# SystemControlCard.net
KiCad netlist of a schematic drawn in EAGLE
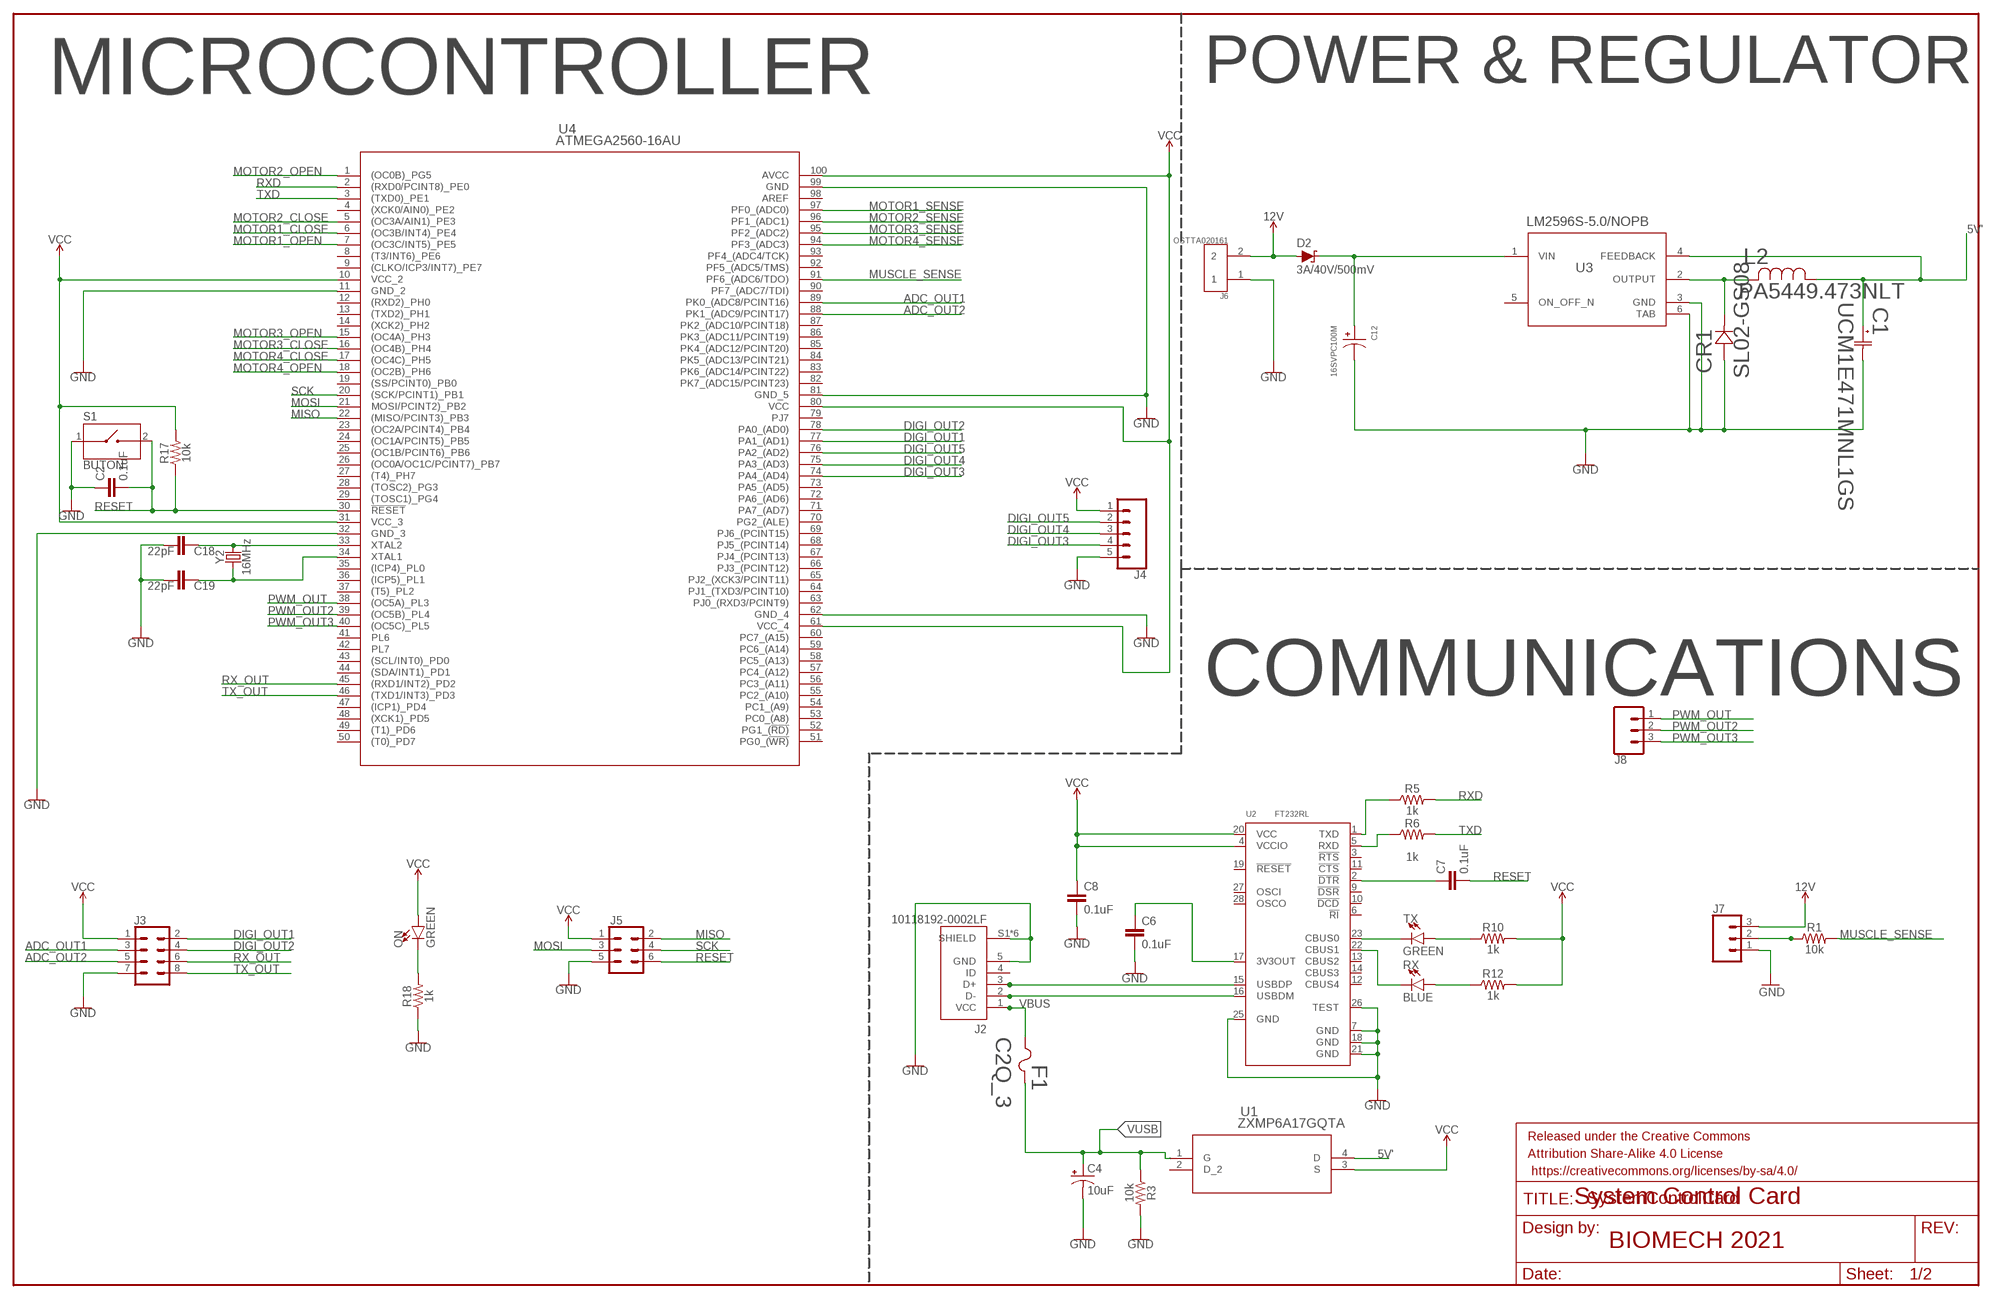
[diagram p0: schematic, sheet 1]
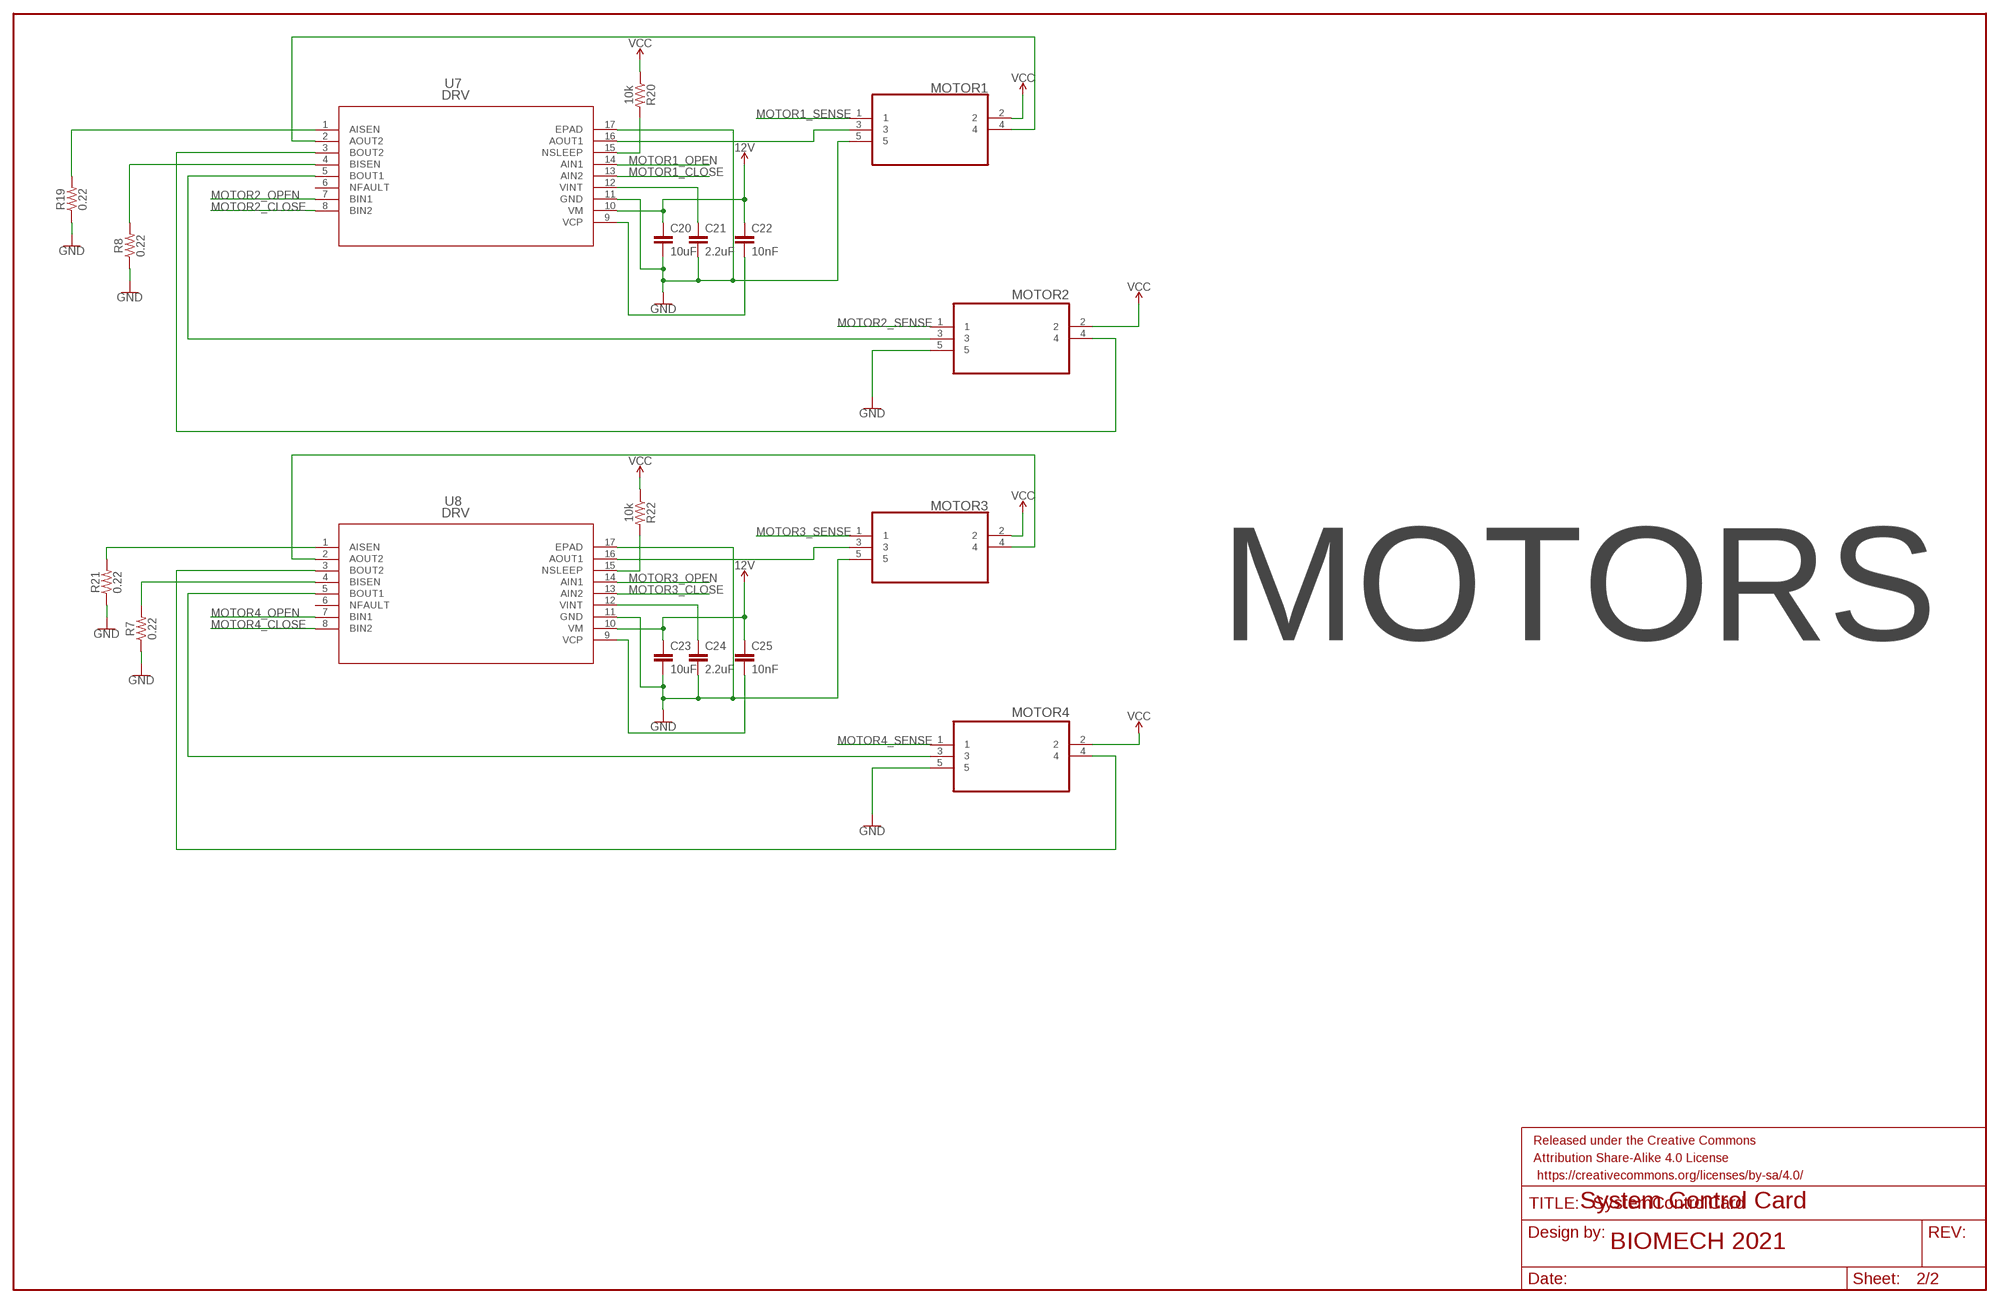
[diagram p1: schematic, sheet 2]

(export (version "E")
  (design (tool "Eeschema 10.0.6"))
  (components
    (comp (ref "C20")
      (value "10uF")
      (footprint "eagle-import:0603")
      (libsource (lib "eagle-import") (part "10UF-0603-6.3V-20%"))
    )
    (comp (ref "C21")
      (value "2.2uF")
      (footprint "eagle-import:0603")
      (libsource (lib "eagle-import") (part "2.2UF-0603-10V-20%"))
    )
    (comp (ref "C22")
      (value "10nF")
      (footprint "eagle-import:0603")
      (libsource (lib "eagle-import") (part "10NF-0603-50V-10%"))
    )
    (comp (ref "C23")
      (value "10uF")
      (footprint "eagle-import:0603")
      (libsource (lib "eagle-import") (part "10UF-0603-6.3V-20%"))
    )
    (comp (ref "C24")
      (value "2.2uF")
      (footprint "eagle-import:0603")
      (libsource (lib "eagle-import") (part "2.2UF-0603-10V-20%"))
    )
    (comp (ref "C25")
      (value "10nF")
      (footprint "eagle-import:0603")
      (libsource (lib "eagle-import") (part "10NF-0603-50V-10%"))
    )
    (comp (ref "FRAME1")
      (value "FRAME-LEDGER")
      (footprint "eagle-import:CREATIVE_COMMONS")
      (fields (field (name "DESIGNED_BY") "BIOMECH 2021") (field (name "TITLE") "System Control Card"))
      (libsource (lib "eagle-import") (part "FRAME-LEDGER"))
    )
    (comp (ref "MOTOR1")
      (value "SFW5R-1STE1LF")
      (footprint "eagle-import:FCI_SFW5R-1STE1LF")
      (fields (field (name "MF") "Amphenol ICC"))
      (libsource (lib "eagle-import") (part "SFW5R-1STE1LF"))
    )
    (comp (ref "MOTOR2")
      (value "SFW5R-1STE1LF")
      (footprint "eagle-import:FCI_SFW5R-1STE1LF")
      (fields (field (name "MF") "Amphenol ICC"))
      (libsource (lib "eagle-import") (part "SFW5R-1STE1LF"))
    )
    (comp (ref "MOTOR3")
      (value "SFW5R-1STE1LF")
      (footprint "eagle-import:FCI_SFW5R-1STE1LF")
      (fields (field (name "MF") "Amphenol ICC"))
      (libsource (lib "eagle-import") (part "SFW5R-1STE1LF"))
    )
    (comp (ref "MOTOR4")
      (value "SFW5R-1STE1LF")
      (footprint "eagle-import:FCI_SFW5R-1STE1LF")
      (fields (field (name "MF") "Amphenol ICC"))
      (libsource (lib "eagle-import") (part "SFW5R-1STE1LF"))
    )
    (comp (ref "R7")
      (value "0.22")
      (footprint "eagle-import:0805")
      (libsource (lib "eagle-import") (part "0.22OHM-0805-1/4W-1%"))
    )
    (comp (ref "R8")
      (value "0.22")
      (footprint "eagle-import:0805")
      (libsource (lib "eagle-import") (part "0.22OHM-0805-1/4W-1%"))
    )
    (comp (ref "R19")
      (value "0.22")
      (footprint "eagle-import:0805")
      (libsource (lib "eagle-import") (part "0.22OHM-0805-1/4W-1%"))
    )
    (comp (ref "R20")
      (value "10k")
      (footprint "eagle-import:0603")
      (libsource (lib "eagle-import") (part "10KOHM-0603-1/10W-1%"))
    )
    (comp (ref "R21")
      (value "0.22")
      (footprint "eagle-import:0805")
      (libsource (lib "eagle-import") (part "0.22OHM-0805-1/4W-1%"))
    )
    (comp (ref "R22")
      (value "10k")
      (footprint "eagle-import:0603")
      (libsource (lib "eagle-import") (part "10KOHM-0603-1/10W-1%"))
    )
    (comp (ref "U7")
      (value "DRV")
      (footprint "eagle-import:RTY16")
      (fields
        (field (name "GENERIC_PART_NUMBER") "DRV8833")
        (field (name "MANUFACTURER") "Texas Instruments")
        (field (name "MANUFACTURER_PART_NUMBER") "DRV8833RTYT")
      )
      (libsource (lib "eagle-import") (part "DRV8833RTYT"))
    )
    (comp (ref "U8")
      (value "DRV")
      (footprint "eagle-import:RTY16")
      (fields
        (field (name "GENERIC_PART_NUMBER") "DRV8833")
        (field (name "MANUFACTURER") "Texas Instruments")
        (field (name "MANUFACTURER_PART_NUMBER") "DRV8833RTYT")
      )
      (libsource (lib "eagle-import") (part "DRV8833RTYT"))
    )
    (comp (ref "C1")
      (value "UCM1E471MNL1GS")
      (footprint "eagle-import:CAP_UCD_8X10_NCH")
      (fields (field (name "COPYRIGHT") "Copyright (C) 2021 Ultra Librarian. All rights reserved."))
      (libsource (lib "eagle-import") (part "UCM1E471MNL1GS"))
    )
    (comp (ref "C2")
      (value "0.1uF")
      (footprint "eagle-import:0603")
      (libsource (lib "eagle-import") (part "0.1UF-0603-25V-5%"))
    )
    (comp (ref "C4")
      (value "10uF")
      (footprint "eagle-import:EIA3216")
      (libsource (lib "eagle-import") (part "10UF-POLAR-EIA3216-16V-10%(TANT)"))
    )
    (comp (ref "C6")
      (value "0.1uF")
      (footprint "eagle-import:0603")
      (libsource (lib "eagle-import") (part "0.1UF-0603-25V-5%"))
    )
    (comp (ref "C7")
      (value "0.1uF")
      (footprint "eagle-import:0603")
      (libsource (lib "eagle-import") (part "0.1UF-0603-25V-5%"))
    )
    (comp (ref "C8")
      (value "0.1uF")
      (footprint "eagle-import:0603")
      (libsource (lib "eagle-import") (part "0.1UF-0603-25V-5%"))
    )
    (comp (ref "C12")
      (value "16SVPC100M")
      (footprint "eagle-import:CAP_16SVPC100M")
      (fields (field (name "MF") "Panasonic"))
      (libsource (lib "eagle-import") (part "16SVPC100M"))
    )
    (comp (ref "C18")
      (value "22pF")
      (footprint "eagle-import:0603")
      (libsource (lib "eagle-import") (part "22PF-0603-50V-5%"))
    )
    (comp (ref "C19")
      (value "22pF")
      (footprint "eagle-import:0603")
      (libsource (lib "eagle-import") (part "22PF-0603-50V-5%"))
    )
    (comp (ref "CR1")
      (value "SL02-GS08")
      (footprint "eagle-import:DIODE_SL02-GS08_VIS")
      (fields (field (name "COPYRIGHT") "Copyright (C) 2021 Ultra Librarian. All rights reserved."))
      (libsource (lib "eagle-import") (part "SL02-GS08"))
    )
    (comp (ref "D2")
      (value "3A/40V/500mV")
      (footprint "eagle-import:SMA-DIODE")
      (libsource (lib "eagle-import") (part "DIODE-SCHOTTKY-B340A"))
    )
    (comp (ref "F1")
      (value "C2Q_3")
      (footprint "eagle-import:C2_BEL")
      (fields
        (field (name "MANUFACTURER_PART_NUMBER") "C2Q 3")
        (field (name "COPYRIGHT") "Copyright (C) 2021 Ultra Librarian. All rights reserved.")
      )
      (libsource (lib "eagle-import") (part "C2Q_3"))
    )
    (comp (ref "FRAME2")
      (value "FRAME-LEDGER")
      (footprint "eagle-import:CREATIVE_COMMONS")
      (fields (field (name "DESIGNED_BY") "BIOMECH 2021") (field (name "TITLE") "System Control Card"))
      (libsource (lib "eagle-import") (part "FRAME-LEDGER"))
    )
    (comp (ref "J2")
      (value "10118192-0002LF")
      (footprint "eagle-import:AMPHENOL_10118192-0002LF")
      (fields (field (name "MF") "Amphenol ICC"))
      (libsource (lib "eagle-import") (part "10118192-0002LF"))
    )
    (comp (ref "J3")
      (value "CONN_04X2")
      (footprint "eagle-import:2X4")
      (libsource (lib "eagle-import") (part "CONN_04X2"))
    )
    (comp (ref "J4")
      (value "CONN_05NO_SILK")
      (footprint "eagle-import:1X05_NO_SILK")
      (libsource (lib "eagle-import") (part "CONN_05NO_SILK"))
    )
    (comp (ref "J5")
      (value "CONN_03X2NO_SILK")
      (footprint "eagle-import:2X3-NS")
      (libsource (lib "eagle-import") (part "CONN_03X2NO_SILK"))
    )
    (comp (ref "J6")
      (value "OSTTA020161")
      (footprint "eagle-import:OST_OSTTA020161")
      (fields (field (name "MF") "On Shore Technology Inc."))
      (libsource (lib "eagle-import") (part "OSTTA020161"))
    )
    (comp (ref "J7")
      (value "CONN_031X03_NO_SILK")
      (footprint "eagle-import:1X03_NO_SILK")
      (libsource (lib "eagle-import") (part "CONN_031X03_NO_SILK"))
    )
    (comp (ref "J8")
      (value "CONN_031X03_NO_SILK")
      (footprint "eagle-import:1X03_NO_SILK")
      (libsource (lib "eagle-import") (part "CONN_031X03_NO_SILK"))
    )
    (comp (ref "L2")
      (value "PA5449.473NLT")
      (footprint "eagle-import:IND_PA5449.473NLT_PUL")
      (fields (field (name "COPYRIGHT") "Copyright (C) 2021 Ultra Librarian. All rights reserved."))
      (libsource (lib "eagle-import") (part "PA5449.473NLT"))
    )
    (comp (ref "ON")
      (value "GREEN")
      (footprint "eagle-import:LED-0603")
      (libsource (lib "eagle-import") (part "LED-GREEN0603"))
    )
    (comp (ref "R1")
      (value "10k")
      (footprint "eagle-import:0603")
      (libsource (lib "eagle-import") (part "10KOHM-0603-1/10W-1%"))
    )
    (comp (ref "R3")
      (value "10k")
      (footprint "eagle-import:0603")
      (libsource (lib "eagle-import") (part "10KOHM-0603-1/10W-1%"))
    )
    (comp (ref "R5")
      (value "1k")
      (footprint "eagle-import:0603")
      (libsource (lib "eagle-import") (part "1KOHM-0603-1/10W-1%"))
    )
    (comp (ref "R6")
      (value "1k")
      (footprint "eagle-import:0603")
      (libsource (lib "eagle-import") (part "1KOHM-0603-1/10W-1%"))
    )
    (comp (ref "R10")
      (value "1k")
      (footprint "eagle-import:0603")
      (libsource (lib "eagle-import") (part "1KOHM-0603-1/10W-1%"))
    )
    (comp (ref "R12")
      (value "1k")
      (footprint "eagle-import:0603")
      (libsource (lib "eagle-import") (part "1KOHM-0603-1/10W-1%"))
    )
    (comp (ref "R17")
      (value "10k")
      (footprint "eagle-import:0603")
      (libsource (lib "eagle-import") (part "10KOHM-0603-1/10W-1%"))
    )
    (comp (ref "R18")
      (value "1k")
      (footprint "eagle-import:0603")
      (libsource (lib "eagle-import") (part "1KOHM-0603-1/10W-1%"))
    )
    (comp (ref "RX")
      (value "BLUE")
      (footprint "eagle-import:LED-0603")
      (libsource (lib "eagle-import") (part "LED-BLUE0603"))
    )
    (comp (ref "S1")
      (value "BUTON")
      (footprint "eagle-import:SW_1437566-4")
      (fields
        (field (name "COMMENT") "1437566-4")
        (field (name "MF") "TE Connectivity")
        (field (name "MP") "FSMSMTR")
      )
      (libsource (lib "eagle-import") (part "1437566-4"))
    )
    (comp (ref "TX")
      (value "GREEN")
      (footprint "eagle-import:LED-0603")
      (libsource (lib "eagle-import") (part "LED-GREEN0603"))
    )
    (comp (ref "U1")
      (value "ZXMP6A17GQTA")
      (footprint "eagle-import:SOT-223_DIO")
      (fields (field (name "COPYRIGHT") "Copyright (C) 2021 Ultra Librarian. All rights reserved."))
      (libsource (lib "eagle-import") (part "ZXMP6A17GQTA"))
    )
    (comp (ref "U2")
      (value "FT232RL")
      (footprint "eagle-import:SSOP28-0.65-10.2X5.2MM")
      (fields (field (name "MF") "FTDI, Future"))
      (libsource (lib "eagle-import") (part "INTERFACE-FT232RL(SSOP28)"))
    )
    (comp (ref "U3")
      (value "LM2596S-5.0/NOPB")
      (footprint "eagle-import:KTT0005B")
      (fields (field (name "COPYRIGHT") "Copyright (C) 2021 Ultra Librarian. All rights reserved."))
      (libsource (lib "eagle-import") (part "LM2596S-5.0/NOPB"))
    )
    (comp (ref "U4")
      (value "ATMEGA2560-16AU")
      (footprint "eagle-import:100A_ATM")
      (libsource (lib "eagle-import") (part "ATMEGA2560-16AU"))
    )
    (comp (ref "Y2")
      (value "16MHz")
      (footprint "eagle-import:HC49US")
      (libsource (lib "eagle-import") (part "CRYSTAL-16MHZPTH-HC49US"))
    )
  )
  (nets
    (net (code "1") (name "5V'") (class "Default")
      (node (ref "C1") (pin "1") (pinfunction "1_1") (pintype "passive"))
      (node (ref "L2") (pin "1") (pinfunction "1_1") (pintype "passive"))
      (node (ref "U1") (pin "4") (pinfunction "D_4") (pintype "passive"))
      (node (ref "U3") (pin "4") (pinfunction "FEEDBACK_4") (pintype "input"))
    )
    (net (code "2") (name "12V") (class "Default")
      (node (ref "C20") (pin "1") (pinfunction "1_1") (pintype "passive"))
      (node (ref "C22") (pin "1") (pinfunction "1_1") (pintype "passive"))
      (node (ref "C23") (pin "1") (pinfunction "1_1") (pintype "passive"))
      (node (ref "C25") (pin "1") (pinfunction "1_1") (pintype "passive"))
      (node (ref "D2") (pin "A") (pinfunction "A_A") (pintype "passive"))
      (node (ref "J6") (pin "2") (pinfunction "2_2") (pintype "passive"))
      (node (ref "J7") (pin "3") (pinfunction "3_3") (pintype "passive"))
      (node (ref "U7") (pin "10") (pinfunction "VM_10") (pintype "power_in"))
      (node (ref "U8") (pin "10") (pinfunction "VM_10") (pintype "power_in"))
    )
    (net (code "3") (name "ADC_OUT1") (class "Default")
      (node (ref "J3") (pin "3") (pinfunction "3_3") (pintype "passive"))
      (node (ref "U4") (pin "89") (pinfunction "PK0_(ADC8/PCINT16)_89") (pintype "bidirectional"))
    )
    (net (code "4") (name "ADC_OUT2") (class "Default")
      (node (ref "J3") (pin "5") (pinfunction "5_5") (pintype "passive"))
      (node (ref "U4") (pin "88") (pinfunction "PK1_(ADC9/PCINT17)_88") (pintype "bidirectional"))
    )
    (net (code "5") (name "AREF") (class "Default")
      (node (ref "U4") (pin "98") (pinfunction "AREF_98") (pintype "power_in"))
    )
    (net (code "6") (name "DIGI_OUT1") (class "Default")
      (node (ref "J3") (pin "2") (pinfunction "2_2") (pintype "passive"))
      (node (ref "U4") (pin "77") (pinfunction "PA1_(AD1)_77") (pintype "bidirectional"))
    )
    (net (code "7") (name "DIGI_OUT2") (class "Default")
      (node (ref "J3") (pin "4") (pinfunction "4_4") (pintype "passive"))
      (node (ref "U4") (pin "78") (pinfunction "PA0_(AD0)_78") (pintype "bidirectional"))
    )
    (net (code "8") (name "DIGI_OUT3") (class "Default")
      (node (ref "J4") (pin "4") (pinfunction "4_4") (pintype "passive"))
      (node (ref "U4") (pin "74") (pinfunction "PA4_(AD4)_74") (pintype "bidirectional"))
    )
    (net (code "9") (name "DIGI_OUT4") (class "Default")
      (node (ref "J4") (pin "3") (pinfunction "3_3") (pintype "passive"))
      (node (ref "U4") (pin "75") (pinfunction "PA3_(AD3)_75") (pintype "bidirectional"))
    )
    (net (code "10") (name "DIGI_OUT5") (class "Default")
      (node (ref "J4") (pin "2") (pinfunction "2_2") (pintype "passive"))
      (node (ref "U4") (pin "76") (pinfunction "PA2_(AD2)_76") (pintype "bidirectional"))
    )
    (net (code "11") (name "GND") (class "Default")
      (node (ref "C1") (pin "2") (pinfunction "2_2") (pintype "passive"))
      (node (ref "C12") (pin "2") (pinfunction "2_2") (pintype "passive"))
      (node (ref "C18") (pin "2") (pinfunction "2_2") (pintype "passive"))
      (node (ref "C19") (pin "2") (pinfunction "2_2") (pintype "passive"))
      (node (ref "C2") (pin "1") (pinfunction "1_1") (pintype "passive"))
      (node (ref "C20") (pin "2") (pinfunction "2_2") (pintype "passive"))
      (node (ref "C21") (pin "2") (pinfunction "2_2") (pintype "passive"))
      (node (ref "C23") (pin "2") (pinfunction "2_2") (pintype "passive"))
      (node (ref "C24") (pin "2") (pinfunction "2_2") (pintype "passive"))
      (node (ref "C4") (pin "-") (pinfunction "-_-") (pintype "passive"))
      (node (ref "C6") (pin "2") (pinfunction "2_2") (pintype "passive"))
      (node (ref "C8") (pin "2") (pinfunction "2_2") (pintype "passive"))
      (node (ref "CR1") (pin "2") (pinfunction "2_2") (pintype "passive"))
      (node (ref "J2") (pin "5") (pinfunction "GND_5") (pintype "power_in"))
      (node (ref "J2") (pin "S1") (pinfunction "SHIELD_S1") (pintype "passive"))
      (node (ref "J2") (pin "S2") (pinfunction "SHIELD_S2") (pintype "passive"))
      (node (ref "J2") (pin "S3") (pinfunction "SHIELD_S3") (pintype "passive"))
      (node (ref "J2") (pin "S4") (pinfunction "SHIELD_S4") (pintype "passive"))
      (node (ref "J2") (pin "S5") (pinfunction "SHIELD_S5") (pintype "passive"))
      (node (ref "J2") (pin "S6") (pinfunction "SHIELD_S6") (pintype "passive"))
      (node (ref "J3") (pin "7") (pinfunction "7_7") (pintype "passive"))
      (node (ref "J4") (pin "5") (pinfunction "5_5") (pintype "passive"))
      (node (ref "J5") (pin "5") (pinfunction "5_5") (pintype "bidirectional"))
      (node (ref "J6") (pin "1") (pinfunction "1_1") (pintype "passive"))
      (node (ref "J7") (pin "1") (pinfunction "1_1") (pintype "passive"))
      (node (ref "MOTOR1") (pin "5") (pinfunction "5_5") (pintype "passive"))
      (node (ref "MOTOR2") (pin "5") (pinfunction "5_5") (pintype "passive"))
      (node (ref "MOTOR3") (pin "5") (pinfunction "5_5") (pintype "passive"))
      (node (ref "MOTOR4") (pin "5") (pinfunction "5_5") (pintype "passive"))
      (node (ref "R18") (pin "1") (pinfunction "1_1") (pintype "passive"))
      (node (ref "R19") (pin "1") (pinfunction "1_1") (pintype "passive"))
      (node (ref "R21") (pin "1") (pinfunction "1_1") (pintype "passive"))
      (node (ref "R3") (pin "2") (pinfunction "2_2") (pintype "passive"))
      (node (ref "R7") (pin "1") (pinfunction "1_1") (pintype "passive"))
      (node (ref "R8") (pin "1") (pinfunction "1_1") (pintype "passive"))
      (node (ref "S1") (pin "1") (pinfunction "1_1") (pintype "passive"))
      (node (ref "U2") (pin "18") (pinfunction "GND_18") (pintype "input"))
      (node (ref "U2") (pin "21") (pinfunction "GND_21") (pintype "input"))
      (node (ref "U2") (pin "25") (pinfunction "GND_25") (pintype "input"))
      (node (ref "U2") (pin "26") (pinfunction "TEST_26") (pintype "input"))
      (node (ref "U2") (pin "7") (pinfunction "GND_7") (pintype "input"))
      (node (ref "U3") (pin "3") (pinfunction "GND_3") (pintype "power_in"))
      (node (ref "U3") (pin "6") (pinfunction "TAB_6") (pintype "power_in"))
      (node (ref "U4") (pin "11") (pinfunction "GND_2_11") (pintype "power_in"))
      (node (ref "U4") (pin "32") (pinfunction "GND_3_32") (pintype "power_in"))
      (node (ref "U4") (pin "62") (pinfunction "GND_4_62") (pintype "power_in"))
      (node (ref "U4") (pin "81") (pinfunction "GND_5_81") (pintype "power_in"))
      (node (ref "U4") (pin "99") (pinfunction "GND_99") (pintype "passive"))
      (node (ref "U7") (pin "11") (pinfunction "GND_11") (pintype "power_in"))
      (node (ref "U7") (pin "17") (pinfunction "EPAD_17") (pintype "passive"))
      (node (ref "U8") (pin "11") (pinfunction "GND_11") (pintype "power_in"))
      (node (ref "U8") (pin "17") (pinfunction "EPAD_17") (pintype "passive"))
    )
    (net (code "12") (name "MISO") (class "Default")
      (node (ref "J5") (pin "2") (pinfunction "2_2") (pintype "bidirectional"))
      (node (ref "U4") (pin "22") (pinfunction "(MISO/PCINT3)_PB3_22") (pintype "bidirectional"))
    )
    (net (code "13") (name "MOSI") (class "Default")
      (node (ref "J5") (pin "3") (pinfunction "3_3") (pintype "bidirectional"))
      (node (ref "U4") (pin "21") (pinfunction "MOSI/PCINT2)_PB2_21") (pintype "bidirectional"))
    )
    (net (code "14") (name "MOTOR1_CLOSE") (class "Default")
      (node (ref "U4") (pin "6") (pinfunction "(OC3B/INT4)_PE4_6") (pintype "bidirectional"))
      (node (ref "U7") (pin "13") (pinfunction "AIN2_13") (pintype "input"))
    )
    (net (code "15") (name "MOTOR1_OPEN") (class "Default")
      (node (ref "U4") (pin "7") (pinfunction "(OC3C/INT5)_PE5_7") (pintype "bidirectional"))
      (node (ref "U7") (pin "14") (pinfunction "AIN1_14") (pintype "input"))
    )
    (net (code "16") (name "MOTOR1_SENSE") (class "Default")
      (node (ref "MOTOR1") (pin "1") (pinfunction "1_1") (pintype "passive"))
      (node (ref "U4") (pin "97") (pinfunction "PF0_(ADC0)_97") (pintype "bidirectional"))
    )
    (net (code "17") (name "MOTOR2_CLOSE") (class "Default")
      (node (ref "U4") (pin "5") (pinfunction "(OC3A/AIN1)_PE3_5") (pintype "bidirectional"))
      (node (ref "U7") (pin "8") (pinfunction "BIN2_8") (pintype "input"))
    )
    (net (code "18") (name "MOTOR2_OPEN") (class "Default")
      (node (ref "U4") (pin "1") (pinfunction "(OC0B)_PG5_1") (pintype "bidirectional"))
      (node (ref "U7") (pin "7") (pinfunction "BIN1_7") (pintype "input"))
    )
    (net (code "19") (name "MOTOR2_SENSE") (class "Default")
      (node (ref "MOTOR2") (pin "1") (pinfunction "1_1") (pintype "passive"))
      (node (ref "U4") (pin "96") (pinfunction "PF1_(ADC1)_96") (pintype "bidirectional"))
    )
    (net (code "20") (name "MOTOR3_CLOSE") (class "Default")
      (node (ref "U4") (pin "16") (pinfunction "(OC4B)_PH4_16") (pintype "bidirectional"))
      (node (ref "U8") (pin "13") (pinfunction "AIN2_13") (pintype "input"))
    )
    (net (code "21") (name "MOTOR3_OPEN") (class "Default")
      (node (ref "U4") (pin "15") (pinfunction "(OC4A)_PH3_15") (pintype "bidirectional"))
      (node (ref "U8") (pin "14") (pinfunction "AIN1_14") (pintype "input"))
    )
    (net (code "22") (name "MOTOR3_SENSE") (class "Default")
      (node (ref "MOTOR3") (pin "1") (pinfunction "1_1") (pintype "passive"))
      (node (ref "U4") (pin "95") (pinfunction "PF2_(ADC2)_95") (pintype "bidirectional"))
    )
    (net (code "23") (name "MOTOR4_CLOSE") (class "Default")
      (node (ref "U4") (pin "17") (pinfunction "(OC4C)_PH5_17") (pintype "bidirectional"))
      (node (ref "U8") (pin "8") (pinfunction "BIN2_8") (pintype "input"))
    )
    (net (code "24") (name "MOTOR4_OPEN") (class "Default")
      (node (ref "U4") (pin "18") (pinfunction "(OC2B)_PH6_18") (pintype "bidirectional"))
      (node (ref "U8") (pin "7") (pinfunction "BIN1_7") (pintype "input"))
    )
    (net (code "25") (name "MOTOR4_SENSE") (class "Default")
      (node (ref "MOTOR4") (pin "1") (pinfunction "1_1") (pintype "passive"))
      (node (ref "U4") (pin "94") (pinfunction "PF3_(ADC3)_94") (pintype "bidirectional"))
    )
    (net (code "26") (name "MUSCLE_SENSE") (class "Default")
      (node (ref "R1") (pin "2") (pinfunction "2_2") (pintype "passive"))
      (node (ref "U4") (pin "91") (pinfunction "PF6_(ADC6/TDO)_91") (pintype "bidirectional"))
    )
    (net (code "27") (name "Net-(J2-D+)") (class "Default")
      (node (ref "J2") (pin "3") (pinfunction "D+_3") (pintype "bidirectional"))
      (node (ref "U2") (pin "15") (pinfunction "USBDP_15") (pintype "input"))
    )
    (net (code "28") (name "Net-(J2-D-)") (class "Default")
      (node (ref "J2") (pin "2") (pinfunction "D-_2") (pintype "bidirectional"))
      (node (ref "U2") (pin "16") (pinfunction "USBDM_16") (pintype "input"))
    )
    (net (code "29") (name "Net-(J7-Pad2)") (class "Default")
      (node (ref "J7") (pin "2") (pinfunction "2_2") (pintype "passive"))
      (node (ref "R1") (pin "1") (pinfunction "1_1") (pintype "passive"))
    )
    (net (code "30") (name "Net-(ON-PadC)") (class "Default")
      (node (ref "ON") (pin "C") (pinfunction "C_C") (pintype "passive"))
      (node (ref "R18") (pin "2") (pinfunction "2_2") (pintype "passive"))
    )
    (net (code "31") (name "Net-(R10-Pad1)") (class "Default")
      (node (ref "R10") (pin "1") (pinfunction "1_1") (pintype "passive"))
      (node (ref "TX") (pin "A") (pinfunction "A_A") (pintype "passive"))
    )
    (net (code "32") (name "Net-(R12-Pad1)") (class "Default")
      (node (ref "R12") (pin "1") (pinfunction "1_1") (pintype "passive"))
      (node (ref "RX") (pin "A") (pinfunction "A_A") (pintype "passive"))
    )
    (net (code "33") (name "Net-(U2-3V3OUT)") (class "Default")
      (node (ref "C6") (pin "1") (pinfunction "1_1") (pintype "passive"))
      (node (ref "U2") (pin "17") (pinfunction "3V3OUT_17") (pintype "input"))
    )
    (net (code "34") (name "Net-(U2-CBUS0)") (class "Default")
      (node (ref "TX") (pin "C") (pinfunction "C_C") (pintype "passive"))
      (node (ref "U2") (pin "23") (pinfunction "CBUS0_23") (pintype "input"))
    )
    (net (code "35") (name "Net-(U2-CBUS1)") (class "Default")
      (node (ref "RX") (pin "C") (pinfunction "C_C") (pintype "passive"))
      (node (ref "U2") (pin "22") (pinfunction "CBUS1_22") (pintype "input"))
    )
    (net (code "36") (name "Net-(U2-RXD)") (class "Default")
      (node (ref "R6") (pin "1") (pinfunction "1_1") (pintype "passive"))
      (node (ref "U2") (pin "5") (pinfunction "RXD_5") (pintype "input"))
    )
    (net (code "37") (name "Net-(U2-TXD)") (class "Default")
      (node (ref "R5") (pin "1") (pinfunction "1_1") (pintype "passive"))
      (node (ref "U2") (pin "1") (pinfunction "TXD_1") (pintype "input"))
    )
    (net (code "38") (name "Net-(U2-~{DTR})") (class "Default")
      (node (ref "C7") (pin "1") (pinfunction "1_1") (pintype "passive"))
      (node (ref "U2") (pin "2") (pinfunction "~{DTR}_2") (pintype "input"))
    )
    (net (code "39") (name "Net-(U3-OUTPUT)") (class "Default")
      (node (ref "CR1") (pin "1") (pinfunction "1_1") (pintype "passive"))
      (node (ref "L2") (pin "2") (pinfunction "2_2") (pintype "passive"))
      (node (ref "U3") (pin "2") (pinfunction "OUTPUT_2") (pintype "power_in"))
    )
    (net (code "40") (name "Net-(U3-VIN)") (class "Default")
      (node (ref "C12") (pin "1") (pinfunction "1_1") (pintype "passive"))
      (node (ref "D2") (pin "C") (pinfunction "C_C") (pintype "passive"))
      (node (ref "U3") (pin "1") (pinfunction "VIN_1") (pintype "power_in"))
    )
    (net (code "41") (name "Net-(U4-XTAL1)") (class "Default")
      (node (ref "C19") (pin "1") (pinfunction "1_1") (pintype "passive"))
      (node (ref "U4") (pin "34") (pinfunction "XTAL1_34") (pintype "input"))
      (node (ref "Y2") (pin "1") (pinfunction "1_1") (pintype "passive"))
    )
    (net (code "42") (name "Net-(U4-XTAL2)") (class "Default")
      (node (ref "C18") (pin "1") (pinfunction "1_1") (pintype "passive"))
      (node (ref "U4") (pin "33") (pinfunction "XTAL2_33") (pintype "output"))
      (node (ref "Y2") (pin "2") (pinfunction "2_2") (pintype "passive"))
    )
    (net (code "43") (name "Net-(U7-AISEN)") (class "Default")
      (node (ref "R19") (pin "2") (pinfunction "2_2") (pintype "passive"))
      (node (ref "U7") (pin "1") (pinfunction "AISEN_1") (pintype "bidirectional"))
    )
    (net (code "44") (name "Net-(U7-AOUT1)") (class "Default")
      (node (ref "MOTOR1") (pin "3") (pinfunction "3_3") (pintype "passive"))
      (node (ref "U7") (pin "16") (pinfunction "AOUT1_16") (pintype "output"))
    )
    (net (code "45") (name "Net-(U7-AOUT2)") (class "Default")
      (node (ref "MOTOR1") (pin "4") (pinfunction "4_4") (pintype "passive"))
      (node (ref "U7") (pin "2") (pinfunction "AOUT2_2") (pintype "output"))
    )
    (net (code "46") (name "Net-(U7-BISEN)") (class "Default")
      (node (ref "R8") (pin "2") (pinfunction "2_2") (pintype "passive"))
      (node (ref "U7") (pin "4") (pinfunction "BISEN_4") (pintype "bidirectional"))
    )
    (net (code "47") (name "Net-(U7-BOUT1)") (class "Default")
      (node (ref "MOTOR2") (pin "3") (pinfunction "3_3") (pintype "passive"))
      (node (ref "U7") (pin "5") (pinfunction "BOUT1_5") (pintype "output"))
    )
    (net (code "48") (name "Net-(U7-BOUT2)") (class "Default")
      (node (ref "MOTOR2") (pin "4") (pinfunction "4_4") (pintype "passive"))
      (node (ref "U7") (pin "3") (pinfunction "BOUT2_3") (pintype "output"))
    )
    (net (code "49") (name "Net-(U7-NSLEEP)") (class "Default")
      (node (ref "R20") (pin "2") (pinfunction "2_2") (pintype "passive"))
      (node (ref "U7") (pin "15") (pinfunction "NSLEEP_15") (pintype "input"))
    )
    (net (code "50") (name "Net-(U7-VCP)") (class "Default")
      (node (ref "C22") (pin "2") (pinfunction "2_2") (pintype "passive"))
      (node (ref "U7") (pin "9") (pinfunction "VCP_9") (pintype "bidirectional"))
    )
    (net (code "51") (name "Net-(U7-VINT)") (class "Default")
      (node (ref "C21") (pin "1") (pinfunction "1_1") (pintype "passive"))
      (node (ref "U7") (pin "12") (pinfunction "VINT_12") (pintype "power_in"))
    )
    (net (code "52") (name "Net-(U8-AISEN)") (class "Default")
      (node (ref "R21") (pin "2") (pinfunction "2_2") (pintype "passive"))
      (node (ref "U8") (pin "1") (pinfunction "AISEN_1") (pintype "bidirectional"))
    )
    (net (code "53") (name "Net-(U8-AOUT1)") (class "Default")
      (node (ref "MOTOR3") (pin "3") (pinfunction "3_3") (pintype "passive"))
      (node (ref "U8") (pin "16") (pinfunction "AOUT1_16") (pintype "output"))
    )
    (net (code "54") (name "Net-(U8-AOUT2)") (class "Default")
      (node (ref "MOTOR3") (pin "4") (pinfunction "4_4") (pintype "passive"))
      (node (ref "U8") (pin "2") (pinfunction "AOUT2_2") (pintype "output"))
    )
    (net (code "55") (name "Net-(U8-BISEN)") (class "Default")
      (node (ref "R7") (pin "2") (pinfunction "2_2") (pintype "passive"))
      (node (ref "U8") (pin "4") (pinfunction "BISEN_4") (pintype "bidirectional"))
    )
    (net (code "56") (name "Net-(U8-BOUT1)") (class "Default")
      (node (ref "MOTOR4") (pin "3") (pinfunction "3_3") (pintype "passive"))
      (node (ref "U8") (pin "5") (pinfunction "BOUT1_5") (pintype "output"))
    )
    (net (code "57") (name "Net-(U8-BOUT2)") (class "Default")
      (node (ref "MOTOR4") (pin "4") (pinfunction "4_4") (pintype "passive"))
      (node (ref "U8") (pin "3") (pinfunction "BOUT2_3") (pintype "output"))
    )
    (net (code "58") (name "Net-(U8-NSLEEP)") (class "Default")
      (node (ref "R22") (pin "2") (pinfunction "2_2") (pintype "passive"))
      (node (ref "U8") (pin "15") (pinfunction "NSLEEP_15") (pintype "input"))
    )
    (net (code "59") (name "Net-(U8-VCP)") (class "Default")
      (node (ref "C25") (pin "2") (pinfunction "2_2") (pintype "passive"))
      (node (ref "U8") (pin "9") (pinfunction "VCP_9") (pintype "bidirectional"))
    )
    (net (code "60") (name "Net-(U8-VINT)") (class "Default")
      (node (ref "C24") (pin "1") (pinfunction "1_1") (pintype "passive"))
      (node (ref "U8") (pin "12") (pinfunction "VINT_12") (pintype "power_in"))
    )
    (net (code "61") (name "PWM_OUT") (class "Default")
      (node (ref "J8") (pin "1") (pinfunction "1_1") (pintype "passive"))
      (node (ref "U4") (pin "38") (pinfunction "(OC5A)_PL3_38") (pintype "bidirectional"))
    )
    (net (code "62") (name "PWM_OUT2") (class "Default")
      (node (ref "J8") (pin "2") (pinfunction "2_2") (pintype "passive"))
      (node (ref "U4") (pin "39") (pinfunction "(OC5B)_PL4_39") (pintype "bidirectional"))
    )
    (net (code "63") (name "PWM_OUT3") (class "Default")
      (node (ref "J8") (pin "3") (pinfunction "3_3") (pintype "passive"))
      (node (ref "U4") (pin "40") (pinfunction "(OC5C)_PL5_40") (pintype "bidirectional"))
    )
    (net (code "64") (name "RESET") (class "Default")
      (node (ref "C2") (pin "2") (pinfunction "2_2") (pintype "passive"))
      (node (ref "C7") (pin "2") (pinfunction "2_2") (pintype "passive"))
      (node (ref "J5") (pin "6") (pinfunction "6_6") (pintype "bidirectional"))
      (node (ref "R17") (pin "1") (pinfunction "1_1") (pintype "passive"))
      (node (ref "S1") (pin "2") (pinfunction "2_2") (pintype "passive"))
      (node (ref "U4") (pin "30") (pinfunction "~{RESET}_30") (pintype "input"))
    )
    (net (code "65") (name "RXD") (class "Default")
      (node (ref "R5") (pin "2") (pinfunction "2_2") (pintype "passive"))
      (node (ref "U4") (pin "2") (pinfunction "(RXD0/PCINT8)_PE0_2") (pintype "bidirectional"))
    )
    (net (code "66") (name "RX_OUT") (class "Default")
      (node (ref "J3") (pin "6") (pinfunction "6_6") (pintype "passive"))
      (node (ref "U4") (pin "45") (pinfunction "(RXD1/INT2)_PD2_45") (pintype "bidirectional"))
    )
    (net (code "67") (name "SCK") (class "Default")
      (node (ref "J5") (pin "4") (pinfunction "4_4") (pintype "bidirectional"))
      (node (ref "U4") (pin "20") (pinfunction "(SCK/PCINT1)_PB1_20") (pintype "bidirectional"))
    )
    (net (code "68") (name "TXD") (class "Default")
      (node (ref "R6") (pin "2") (pinfunction "2_2") (pintype "passive"))
      (node (ref "U4") (pin "3") (pinfunction "(TXD0)_PE1_3") (pintype "bidirectional"))
    )
    (net (code "69") (name "TX_OUT") (class "Default")
      (node (ref "J3") (pin "8") (pinfunction "8_8") (pintype "passive"))
      (node (ref "U4") (pin "46") (pinfunction "(TXD1/INT3)_PD3_46") (pintype "bidirectional"))
    )
    (net (code "70") (name "VBUS") (class "Default")
      (node (ref "F1") (pin "1") (pinfunction "1_1") (pintype "passive"))
      (node (ref "J2") (pin "1") (pinfunction "VCC_1") (pintype "power_in"))
    )
    (net (code "71") (name "VCC") (class "Default")
      (node (ref "C8") (pin "1") (pinfunction "1_1") (pintype "passive"))
      (node (ref "J3") (pin "1") (pinfunction "1_1") (pintype "passive"))
      (node (ref "J4") (pin "1") (pinfunction "1_1") (pintype "passive"))
      (node (ref "J5") (pin "1") (pinfunction "1_1") (pintype "bidirectional"))
      (node (ref "MOTOR1") (pin "2") (pinfunction "2_2") (pintype "passive"))
      (node (ref "MOTOR2") (pin "2") (pinfunction "2_2") (pintype "passive"))
      (node (ref "MOTOR3") (pin "2") (pinfunction "2_2") (pintype "passive"))
      (node (ref "MOTOR4") (pin "2") (pinfunction "2_2") (pintype "passive"))
      (node (ref "ON") (pin "A") (pinfunction "A_A") (pintype "passive"))
      (node (ref "R10") (pin "2") (pinfunction "2_2") (pintype "passive"))
      (node (ref "R12") (pin "2") (pinfunction "2_2") (pintype "passive"))
      (node (ref "R17") (pin "2") (pinfunction "2_2") (pintype "passive"))
      (node (ref "R20") (pin "1") (pinfunction "1_1") (pintype "passive"))
      (node (ref "R22") (pin "1") (pinfunction "1_1") (pintype "passive"))
      (node (ref "U1") (pin "3") (pinfunction "S_3") (pintype "passive"))
      (node (ref "U2") (pin "20") (pinfunction "VCC_20") (pintype "input"))
      (node (ref "U2") (pin "4") (pinfunction "VCCIO_4") (pintype "input"))
      (node (ref "U4") (pin "10") (pinfunction "VCC_2_10") (pintype "power_in"))
      (node (ref "U4") (pin "100") (pinfunction "AVCC_100") (pintype "power_in"))
      (node (ref "U4") (pin "31") (pinfunction "VCC_3_31") (pintype "power_in"))
      (node (ref "U4") (pin "61") (pinfunction "VCC_4_61") (pintype "power_in"))
      (node (ref "U4") (pin "80") (pinfunction "VCC_80") (pintype "power_in"))
    )
    (net (code "72") (name "VUSB") (class "Default")
      (node (ref "C4") (pin "+") (pinfunction "+_+") (pintype "passive"))
      (node (ref "F1") (pin "2") (pinfunction "2_2") (pintype "passive"))
      (node (ref "R3") (pin "1") (pinfunction "1_1") (pintype "passive"))
      (node (ref "U1") (pin "1") (pinfunction "G_1") (pintype "passive"))
    )
    (net (code "73") (name "unconnected-(J2-ID-Pad4)") (class "Default")
      (node (ref "J2") (pin "4") (pinfunction "ID_4") (pintype "bidirectional"))
    )
    (net (code "74") (name "unconnected-(U1-D_2-Pad2)") (class "Default")
      (node (ref "U1") (pin "2") (pinfunction "D_2_2") (pintype "passive"))
    )
    (net (code "75") (name "unconnected-(U2-CBUS2-Pad13)") (class "Default")
      (node (ref "U2") (pin "13") (pinfunction "CBUS2_13") (pintype "input"))
    )
    (net (code "76") (name "unconnected-(U2-CBUS3-Pad14)") (class "Default")
      (node (ref "U2") (pin "14") (pinfunction "CBUS3_14") (pintype "input"))
    )
    (net (code "77") (name "unconnected-(U2-CBUS4-Pad12)") (class "Default")
      (node (ref "U2") (pin "12") (pinfunction "CBUS4_12") (pintype "input"))
    )
    (net (code "78") (name "unconnected-(U2-OSCI-Pad27)") (class "Default")
      (node (ref "U2") (pin "27") (pinfunction "OSCI_27") (pintype "input"))
    )
    (net (code "79") (name "unconnected-(U2-OSCO-Pad28)") (class "Default")
      (node (ref "U2") (pin "28") (pinfunction "OSCO_28") (pintype "input"))
    )
    (net (code "80") (name "unconnected-(U2-~{CTS}-Pad11)") (class "Default")
      (node (ref "U2") (pin "11") (pinfunction "~{CTS}_11") (pintype "input"))
    )
    (net (code "81") (name "unconnected-(U2-~{DCD}-Pad10)") (class "Default")
      (node (ref "U2") (pin "10") (pinfunction "~{DCD}_10") (pintype "input"))
    )
    (net (code "82") (name "unconnected-(U2-~{DSR}-Pad9)") (class "Default")
      (node (ref "U2") (pin "9") (pinfunction "~{DSR}_9") (pintype "input"))
    )
    (net (code "83") (name "unconnected-(U2-~{RESET}-Pad19)") (class "Default")
      (node (ref "U2") (pin "19") (pinfunction "~{RESET}_19") (pintype "input"))
    )
    (net (code "84") (name "unconnected-(U2-~{RI}-Pad6)") (class "Default")
      (node (ref "U2") (pin "6") (pinfunction "~{RI}_6") (pintype "input"))
    )
    (net (code "85") (name "unconnected-(U2-~{RTS}-Pad3)") (class "Default")
      (node (ref "U2") (pin "3") (pinfunction "~{RTS}_3") (pintype "input"))
    )
    (net (code "86") (name "unconnected-(U3-ON_OFF_N-Pad5)") (class "Default")
      (node (ref "U3") (pin "5") (pinfunction "ON_OFF_N_5") (pintype "input"))
    )
    (net (code "87") (name "unconnected-(U4-(CLKO{slash}ICP3{slash}INT7)_PE7-Pad9)") (class "Default")
      (node (ref "U4") (pin "9") (pinfunction "(CLKO/ICP3/INT7)_PE7_9") (pintype "bidirectional"))
    )
    (net (code "88") (name "unconnected-(U4-(ICP1)_PD4-Pad47)") (class "Default")
      (node (ref "U4") (pin "47") (pinfunction "(ICP1)_PD4_47") (pintype "bidirectional"))
    )
    (net (code "89") (name "unconnected-(U4-(ICP4)_PL0-Pad35)") (class "Default")
      (node (ref "U4") (pin "35") (pinfunction "(ICP4)_PL0_35") (pintype "bidirectional"))
    )
    (net (code "90") (name "unconnected-(U4-(ICP5)_PL1-Pad36)") (class "Default")
      (node (ref "U4") (pin "36") (pinfunction "(ICP5)_PL1_36") (pintype "bidirectional"))
    )
    (net (code "91") (name "unconnected-(U4-(OC0A{slash}OC1C{slash}PCINT7)_PB7-Pad26)") (class "Default")
      (node (ref "U4") (pin "26") (pinfunction "(OC0A/OC1C/PCINT7)_PB7_26") (pintype "bidirectional"))
    )
    (net (code "92") (name "unconnected-(U4-(OC1A{slash}PCINT5)_PB5-Pad24)") (class "Default")
      (node (ref "U4") (pin "24") (pinfunction "(OC1A/PCINT5)_PB5_24") (pintype "bidirectional"))
    )
    (net (code "93") (name "unconnected-(U4-(OC1B{slash}PCINT6)_PB6-Pad25)") (class "Default")
      (node (ref "U4") (pin "25") (pinfunction "(OC1B/PCINT6)_PB6_25") (pintype "bidirectional"))
    )
    (net (code "94") (name "unconnected-(U4-(OC2A{slash}PCINT4)_PB4-Pad23)") (class "Default")
      (node (ref "U4") (pin "23") (pinfunction "(OC2A/PCINT4)_PB4_23") (pintype "bidirectional"))
    )
    (net (code "95") (name "unconnected-(U4-(RXD2)_PH0-Pad12)") (class "Default")
      (node (ref "U4") (pin "12") (pinfunction "(RXD2)_PH0_12") (pintype "bidirectional"))
    )
    (net (code "96") (name "unconnected-(U4-(SCL{slash}INT0)_PD0-Pad43)") (class "Default")
      (node (ref "U4") (pin "43") (pinfunction "(SCL/INT0)_PD0_43") (pintype "bidirectional"))
    )
    (net (code "97") (name "unconnected-(U4-(SDA{slash}INT1)_PD1-Pad44)") (class "Default")
      (node (ref "U4") (pin "44") (pinfunction "(SDA/INT1)_PD1_44") (pintype "bidirectional"))
    )
    (net (code "98") (name "unconnected-(U4-(SS{slash}PCINT0)_PB0-Pad19)") (class "Default")
      (node (ref "U4") (pin "19") (pinfunction "(SS/PCINT0)_PB0_19") (pintype "bidirectional"))
    )
    (net (code "99") (name "unconnected-(U4-(T0)_PD7-Pad50)") (class "Default")
      (node (ref "U4") (pin "50") (pinfunction "(T0)_PD7_50") (pintype "bidirectional"))
    )
    (net (code "100") (name "unconnected-(U4-(T1)_PD6-Pad49)") (class "Default")
      (node (ref "U4") (pin "49") (pinfunction "(T1)_PD6_49") (pintype "bidirectional"))
    )
    (net (code "101") (name "unconnected-(U4-(T3{slash}INT6)_PE6-Pad8)") (class "Default")
      (node (ref "U4") (pin "8") (pinfunction "(T3/INT6)_PE6_8") (pintype "bidirectional"))
    )
    (net (code "102") (name "unconnected-(U4-(T4)_PH7-Pad27)") (class "Default")
      (node (ref "U4") (pin "27") (pinfunction "(T4)_PH7_27") (pintype "bidirectional"))
    )
    (net (code "103") (name "unconnected-(U4-(T5)_PL2-Pad37)") (class "Default")
      (node (ref "U4") (pin "37") (pinfunction "(T5)_PL2_37") (pintype "bidirectional"))
    )
    (net (code "104") (name "unconnected-(U4-(TOSC1)_PG4-Pad29)") (class "Default")
      (node (ref "U4") (pin "29") (pinfunction "(TOSC1)_PG4_29") (pintype "bidirectional"))
    )
    (net (code "105") (name "unconnected-(U4-(TOSC2)_PG3-Pad28)") (class "Default")
      (node (ref "U4") (pin "28") (pinfunction "(TOSC2)_PG3_28") (pintype "bidirectional"))
    )
    (net (code "106") (name "unconnected-(U4-(TXD2)_PH1-Pad13)") (class "Default")
      (node (ref "U4") (pin "13") (pinfunction "(TXD2)_PH1_13") (pintype "bidirectional"))
    )
    (net (code "107") (name "unconnected-(U4-(XCK0{slash}AIN0)_PE2-Pad4)") (class "Default")
      (node (ref "U4") (pin "4") (pinfunction "(XCK0/AIN0)_PE2_4") (pintype "bidirectional"))
    )
    (net (code "108") (name "unconnected-(U4-(XCK1)_PD5-Pad48)") (class "Default")
      (node (ref "U4") (pin "48") (pinfunction "(XCK1)_PD5_48") (pintype "bidirectional"))
    )
    (net (code "109") (name "unconnected-(U4-(XCK2)_PH2-Pad14)") (class "Default")
      (node (ref "U4") (pin "14") (pinfunction "(XCK2)_PH2_14") (pintype "bidirectional"))
    )
    (net (code "110") (name "unconnected-(U4-PA5_(AD5)-Pad73)") (class "Default")
      (node (ref "U4") (pin "73") (pinfunction "PA5_(AD5)_73") (pintype "bidirectional"))
    )
    (net (code "111") (name "unconnected-(U4-PA6_(AD6)-Pad72)") (class "Default")
      (node (ref "U4") (pin "72") (pinfunction "PA6_(AD6)_72") (pintype "bidirectional"))
    )
    (net (code "112") (name "unconnected-(U4-PA7_(AD7)-Pad71)") (class "Default")
      (node (ref "U4") (pin "71") (pinfunction "PA7_(AD7)_71") (pintype "bidirectional"))
    )
    (net (code "113") (name "unconnected-(U4-PC0_(A8)-Pad53)") (class "Default")
      (node (ref "U4") (pin "53") (pinfunction "PC0_(A8)_53") (pintype "bidirectional"))
    )
    (net (code "114") (name "unconnected-(U4-PC1_(A9)-Pad54)") (class "Default")
      (node (ref "U4") (pin "54") (pinfunction "PC1_(A9)_54") (pintype "bidirectional"))
    )
    (net (code "115") (name "unconnected-(U4-PC2_(A10)-Pad55)") (class "Default")
      (node (ref "U4") (pin "55") (pinfunction "PC2_(A10)_55") (pintype "bidirectional"))
    )
    (net (code "116") (name "unconnected-(U4-PC3_(A11)-Pad56)") (class "Default")
      (node (ref "U4") (pin "56") (pinfunction "PC3_(A11)_56") (pintype "bidirectional"))
    )
    (net (code "117") (name "unconnected-(U4-PC4_(A12)-Pad57)") (class "Default")
      (node (ref "U4") (pin "57") (pinfunction "PC4_(A12)_57") (pintype "bidirectional"))
    )
    (net (code "118") (name "unconnected-(U4-PC5_(A13)-Pad58)") (class "Default")
      (node (ref "U4") (pin "58") (pinfunction "PC5_(A13)_58") (pintype "bidirectional"))
    )
    (net (code "119") (name "unconnected-(U4-PC6_(A14)-Pad59)") (class "Default")
      (node (ref "U4") (pin "59") (pinfunction "PC6_(A14)_59") (pintype "bidirectional"))
    )
    (net (code "120") (name "unconnected-(U4-PC7_(A15)-Pad60)") (class "Default")
      (node (ref "U4") (pin "60") (pinfunction "PC7_(A15)_60") (pintype "bidirectional"))
    )
    (net (code "121") (name "unconnected-(U4-PF4_(ADC4{slash}TCK)-Pad93)") (class "Default")
      (node (ref "U4") (pin "93") (pinfunction "PF4_(ADC4/TCK)_93") (pintype "bidirectional"))
    )
    (net (code "122") (name "unconnected-(U4-PF5_(ADC5{slash}TMS)-Pad92)") (class "Default")
      (node (ref "U4") (pin "92") (pinfunction "PF5_(ADC5/TMS)_92") (pintype "bidirectional"))
    )
    (net (code "123") (name "unconnected-(U4-PF7_(ADC7{slash}TDI)-Pad90)") (class "Default")
      (node (ref "U4") (pin "90") (pinfunction "PF7_(ADC7/TDI)_90") (pintype "bidirectional"))
    )
    (net (code "124") (name "unconnected-(U4-PG0_(~{WR})-Pad51)") (class "Default")
      (node (ref "U4") (pin "51") (pinfunction "PG0_(~{WR})_51") (pintype "bidirectional"))
    )
    (net (code "125") (name "unconnected-(U4-PG1_(~{RD})-Pad52)") (class "Default")
      (node (ref "U4") (pin "52") (pinfunction "PG1_(~{RD})_52") (pintype "bidirectional"))
    )
    (net (code "126") (name "unconnected-(U4-PG2_(ALE)-Pad70)") (class "Default")
      (node (ref "U4") (pin "70") (pinfunction "PG2_(ALE)_70") (pintype "bidirectional"))
    )
    (net (code "127") (name "unconnected-(U4-PJ0_(RXD3{slash}PCINT9)-Pad63)") (class "Default")
      (node (ref "U4") (pin "63") (pinfunction "PJ0_(RXD3/PCINT9)_63") (pintype "bidirectional"))
    )
    (net (code "128") (name "unconnected-(U4-PJ1_(TXD3{slash}PCINT10)-Pad64)") (class "Default")
      (node (ref "U4") (pin "64") (pinfunction "PJ1_(TXD3/PCINT10)_64") (pintype "bidirectional"))
    )
    (net (code "129") (name "unconnected-(U4-PJ2_(XCK3{slash}PCINT11)-Pad65)") (class "Default")
      (node (ref "U4") (pin "65") (pinfunction "PJ2_(XCK3/PCINT11)_65") (pintype "bidirectional"))
    )
    (net (code "130") (name "unconnected-(U4-PJ3_(PCINT12)-Pad66)") (class "Default")
      (node (ref "U4") (pin "66") (pinfunction "PJ3_(PCINT12)_66") (pintype "bidirectional"))
    )
    (net (code "131") (name "unconnected-(U4-PJ4_(PCINT13)-Pad67)") (class "Default")
      (node (ref "U4") (pin "67") (pinfunction "PJ4_(PCINT13)_67") (pintype "bidirectional"))
    )
    (net (code "132") (name "unconnected-(U4-PJ5_(PCINT14)-Pad68)") (class "Default")
      (node (ref "U4") (pin "68") (pinfunction "PJ5_(PCINT14)_68") (pintype "bidirectional"))
    )
    (net (code "133") (name "unconnected-(U4-PJ6_(PCINT15)-Pad69)") (class "Default")
      (node (ref "U4") (pin "69") (pinfunction "PJ6_(PCINT15)_69") (pintype "bidirectional"))
    )
    (net (code "134") (name "unconnected-(U4-PJ7-Pad79)") (class "Default")
      (node (ref "U4") (pin "79") (pinfunction "PJ7_79") (pintype "bidirectional"))
    )
    (net (code "135") (name "unconnected-(U4-PK2_(ADC10{slash}PCINT18)-Pad87)") (class "Default")
      (node (ref "U4") (pin "87") (pinfunction "PK2_(ADC10/PCINT18)_87") (pintype "bidirectional"))
    )
    (net (code "136") (name "unconnected-(U4-PK3_(ADC11{slash}PCINT19)-Pad86)") (class "Default")
      (node (ref "U4") (pin "86") (pinfunction "PK3_(ADC11/PCINT19)_86") (pintype "bidirectional"))
    )
    (net (code "137") (name "unconnected-(U4-PK4_(ADC12{slash}PCINT20)-Pad85)") (class "Default")
      (node (ref "U4") (pin "85") (pinfunction "PK4_(ADC12/PCINT20)_85") (pintype "bidirectional"))
    )
    (net (code "138") (name "unconnected-(U4-PK5_(ADC13{slash}PCINT21)-Pad84)") (class "Default")
      (node (ref "U4") (pin "84") (pinfunction "PK5_(ADC13/PCINT21)_84") (pintype "bidirectional"))
    )
    (net (code "139") (name "unconnected-(U4-PK6_(ADC14{slash}PCINT22)-Pad83)") (class "Default")
      (node (ref "U4") (pin "83") (pinfunction "PK6_(ADC14/PCINT22)_83") (pintype "bidirectional"))
    )
    (net (code "140") (name "unconnected-(U4-PK7_(ADC15{slash}PCINT23)-Pad82)") (class "Default")
      (node (ref "U4") (pin "82") (pinfunction "PK7_(ADC15/PCINT23)_82") (pintype "bidirectional"))
    )
    (net (code "141") (name "unconnected-(U4-PL6-Pad41)") (class "Default")
      (node (ref "U4") (pin "41") (pinfunction "PL6_41") (pintype "bidirectional"))
    )
    (net (code "142") (name "unconnected-(U4-PL7-Pad42)") (class "Default")
      (node (ref "U4") (pin "42") (pinfunction "PL7_42") (pintype "bidirectional"))
    )
    (net (code "143") (name "unconnected-(U7-NFAULT-Pad6)") (class "Default")
      (node (ref "U7") (pin "6") (pinfunction "NFAULT_6") (pintype "output"))
    )
    (net (code "144") (name "unconnected-(U8-NFAULT-Pad6)") (class "Default")
      (node (ref "U8") (pin "6") (pinfunction "NFAULT_6") (pintype "output"))
    )
  )
)
